# protection.net
KiCad netlist of a schematic drawn in Altium Designer
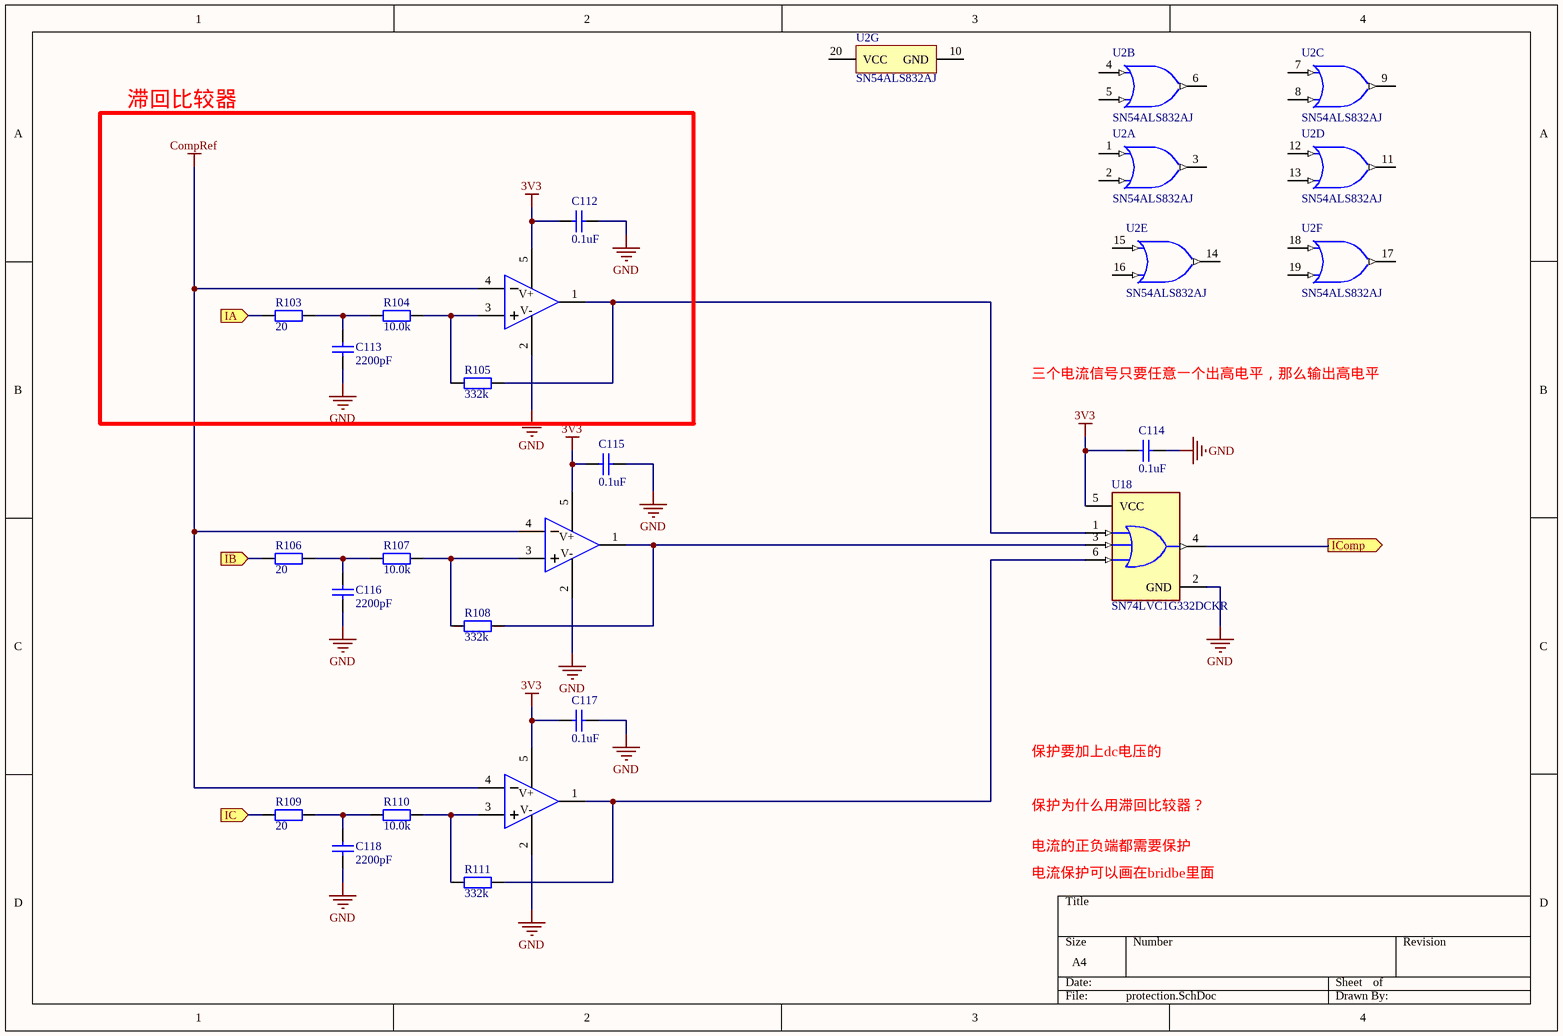
[diagram p0: protection.SchDoc]

(export (version "E")
  (design (tool "Eeschema 10.0.6"))
  (components
    (comp (ref "C112")
      (value "0.1uF")
      (footprint "CAPC1608X06N")
      (description "Capacitor")
      (fields (field (name "PUBLISHER") "Altium Limited"))
      (libsource (lib "Simscale") (part "Cap"))
    )
    (comp (ref "C113")
      (value "2200pF")
      (footprint "CAPC1608X06N")
      (description "Capacitor")
      (fields (field (name "PUBLISHER") "Altium Limited"))
      (libsource (lib "Simscale") (part "Cap"))
    )
    (comp (ref "C114")
      (value "0.1uF")
      (footprint "CAPC1608X06N")
      (description "Capacitor")
      (fields (field (name "PUBLISHER") "Altium Limited"))
      (libsource (lib "Simscale") (part "Cap"))
    )
    (comp (ref "C115")
      (value "0.1uF")
      (footprint "CAPC1608X06N")
      (description "Capacitor")
      (fields (field (name "PUBLISHER") "Altium Limited"))
      (libsource (lib "Simscale") (part "Cap"))
    )
    (comp (ref "C116")
      (value "2200pF")
      (footprint "CAPC1608X06N")
      (description "Capacitor")
      (fields (field (name "PUBLISHER") "Altium Limited"))
      (libsource (lib "Simscale") (part "Cap"))
    )
    (comp (ref "C117")
      (value "0.1uF")
      (footprint "CAPC1608X06N")
      (description "Capacitor")
      (fields (field (name "PUBLISHER") "Altium Limited"))
      (libsource (lib "Simscale") (part "Cap"))
    )
    (comp (ref "C118")
      (value "2200pF")
      (footprint "CAPC1608X06N")
      (description "Capacitor")
      (fields (field (name "PUBLISHER") "Altium Limited"))
      (libsource (lib "Simscale") (part "Cap"))
    )
    (comp (ref "R103")
      (value "20")
      (footprint "RESC1608X05N")
      (description "贴片电阻")
      (libsource (lib "Simscale") (part "0603 100KΩ (1003) 1%_4"))
    )
    (comp (ref "R104")
      (value "10.0k")
      (footprint "RESC1608X05N")
      (description "贴片电阻")
      (libsource (lib "Simscale") (part "0603 100KΩ (1003) 1%_4"))
    )
    (comp (ref "R105")
      (value "332k")
      (footprint "RESC1608X05N")
      (description "贴片电阻")
      (libsource (lib "Simscale") (part "0603 100KΩ (1003) 1%_4"))
    )
    (comp (ref "R106")
      (value "20")
      (footprint "RESC1608X05N")
      (description "贴片电阻")
      (libsource (lib "Simscale") (part "0603 100KΩ (1003) 1%_4"))
    )
    (comp (ref "R107")
      (value "10.0k")
      (footprint "RESC1608X05N")
      (description "贴片电阻")
      (libsource (lib "Simscale") (part "0603 100KΩ (1003) 1%_4"))
    )
    (comp (ref "R108")
      (value "332k")
      (footprint "RESC1608X05N")
      (description "贴片电阻")
      (libsource (lib "Simscale") (part "0603 100KΩ (1003) 1%_4"))
    )
    (comp (ref "R109")
      (value "20")
      (footprint "RESC1608X05N")
      (description "贴片电阻")
      (libsource (lib "Simscale") (part "0603 100KΩ (1003) 1%_4"))
    )
    (comp (ref "R110")
      (value "10.0k")
      (footprint "RESC1608X05N")
      (description "贴片电阻")
      (libsource (lib "Simscale") (part "0603 100KΩ (1003) 1%_4"))
    )
    (comp (ref "R111")
      (value "332k")
      (footprint "RESC1608X05N")
      (description "贴片电阻")
      (libsource (lib "Simscale") (part "0603 100KΩ (1003) 1%_4"))
    )
    (comp (ref "U2")
      (value "SN54ALS832AJ")
      (footprint "J0020A")
      (description "Hex 2-Input OR Drivers, J0020A, TUBE")
      (fields
        (field (name "MANUFACTURER") "Texas Instruments")
        (field (name "GENERIC PART NUMBER") "SN54ALS832A")
      )
      (libsource (lib "Altium Content Vault") (part "TI-SNX4AXX832X-20"))
    )
    (comp (ref "U17")
      (value "TLV3201AIDBVR")
      (footprint "SOT-23-5_L3.0-W1.7-P0.95-LS2.8-BR")
      (fields (field (name "MANUFACTURER") "TI(德州仪器)"))
      (libsource (lib "TLV3201AIDBVR1_TLV3201AIDBVR.schdoc") (part "TLV3201AIDBVR"))
    )
    (comp (ref "U18")
      (value "SN74LVC1G332DCKR")
      (footprint "FP-DCK0006A-MFG")
      (description "IC GATE OR 1CH 3-INP SC70-6")
      (fields
        (field (name "MANUFACTURER") "Texas Instruments")
        (field (name "OCTOPART") "https://octopart.com/sn74lvc1g332dckr-texas+instruments-464861")
      )
      (libsource (lib "Altium Content Vault") (part "a1fbee6839145229a27344b52c53a8d"))
    )
    (comp (ref "U19")
      (value "TLV3201AIDBVR")
      (footprint "SOT-23-5_L3.0-W1.7-P0.95-LS2.8-BR")
      (fields (field (name "MANUFACTURER") "TI(德州仪器)"))
      (libsource (lib "TLV3201AIDBVR1_TLV3201AIDBVR.schdoc") (part "TLV3201AIDBVR"))
    )
    (comp (ref "U20")
      (value "TLV3201AIDBVR")
      (footprint "SOT-23-5_L3.0-W1.7-P0.95-LS2.8-BR")
      (fields (field (name "MANUFACTURER") "TI(德州仪器)"))
      (libsource (lib "TLV3201AIDBVR1_TLV3201AIDBVR.schdoc") (part "TLV3201AIDBVR"))
    )
  )
  (nets
    (net (code "1") (name "/IA") (class "Default")
      (node (ref "R103") (pin "2") (pinfunction "2_2") (pintype "passive"))
    )
    (net (code "2") (name "/IB") (class "Default")
      (node (ref "R106") (pin "2") (pinfunction "2_2") (pintype "passive"))
    )
    (net (code "3") (name "/IC") (class "Default")
      (node (ref "R109") (pin "2") (pinfunction "2_2") (pintype "passive"))
    )
    (net (code "4") (name "/IComp") (class "Default")
      (node (ref "U18") (pin "4") (pinfunction "Y_4") (pintype "output"))
    )
    (net (code "5") (name "3V3") (class "Default")
      (node (ref "C112") (pin "1") (pinfunction "1_1") (pintype "passive"))
      (node (ref "C114") (pin "1") (pinfunction "1_1") (pintype "passive"))
      (node (ref "C115") (pin "1") (pinfunction "1_1") (pintype "passive"))
      (node (ref "C117") (pin "1") (pinfunction "1_1") (pintype "passive"))
      (node (ref "U17") (pin "5") (pinfunction "VCC_5") (pintype "passive"))
      (node (ref "U18") (pin "5") (pinfunction "VCC_5") (pintype "power_in"))
      (node (ref "U19") (pin "5") (pinfunction "VCC_5") (pintype "passive"))
      (node (ref "U20") (pin "5") (pinfunction "VCC_5") (pintype "passive"))
    )
    (net (code "6") (name "CompRef") (class "Default")
      (node (ref "U17") (pin "4") (pinfunction "IN-_4") (pintype "passive"))
      (node (ref "U19") (pin "4") (pinfunction "IN-_4") (pintype "passive"))
      (node (ref "U20") (pin "4") (pinfunction "IN-_4") (pintype "passive"))
    )
    (net (code "7") (name "GND") (class "Default")
      (node (ref "C112") (pin "2") (pinfunction "2_2") (pintype "passive"))
      (node (ref "C113") (pin "2") (pinfunction "2_2") (pintype "passive"))
      (node (ref "C114") (pin "2") (pinfunction "2_2") (pintype "passive"))
      (node (ref "C115") (pin "2") (pinfunction "2_2") (pintype "passive"))
      (node (ref "C116") (pin "2") (pinfunction "2_2") (pintype "passive"))
      (node (ref "C117") (pin "2") (pinfunction "2_2") (pintype "passive"))
      (node (ref "C118") (pin "2") (pinfunction "2_2") (pintype "passive"))
      (node (ref "U17") (pin "2") (pinfunction "GND_2") (pintype "passive"))
      (node (ref "U18") (pin "2") (pinfunction "GND_2") (pintype "power_in"))
      (node (ref "U19") (pin "2") (pinfunction "GND_2") (pintype "passive"))
      (node (ref "U20") (pin "2") (pinfunction "GND_2") (pintype "passive"))
    )
    (net (code "8") (name "Net-(C113-Pad1)") (class "Default")
      (node (ref "C113") (pin "1") (pinfunction "1_1") (pintype "passive"))
      (node (ref "R103") (pin "1") (pinfunction "1_1") (pintype "passive"))
      (node (ref "R104") (pin "2") (pinfunction "2_2") (pintype "passive"))
    )
    (net (code "9") (name "Net-(C116-Pad1)") (class "Default")
      (node (ref "C116") (pin "1") (pinfunction "1_1") (pintype "passive"))
      (node (ref "R106") (pin "1") (pinfunction "1_1") (pintype "passive"))
      (node (ref "R107") (pin "2") (pinfunction "2_2") (pintype "passive"))
    )
    (net (code "10") (name "Net-(C118-Pad1)") (class "Default")
      (node (ref "C118") (pin "1") (pinfunction "1_1") (pintype "passive"))
      (node (ref "R109") (pin "1") (pinfunction "1_1") (pintype "passive"))
      (node (ref "R110") (pin "2") (pinfunction "2_2") (pintype "passive"))
    )
    (net (code "11") (name "Net-(U17-IN+)") (class "Default")
      (node (ref "R104") (pin "1") (pinfunction "1_1") (pintype "passive"))
      (node (ref "R105") (pin "2") (pinfunction "2_2") (pintype "passive"))
      (node (ref "U17") (pin "3") (pinfunction "IN+_3") (pintype "passive"))
    )
    (net (code "12") (name "Net-(U17-OUT)") (class "Default")
      (node (ref "R105") (pin "1") (pinfunction "1_1") (pintype "passive"))
      (node (ref "U17") (pin "1") (pinfunction "OUT_1") (pintype "passive"))
      (node (ref "U18") (pin "1") (pinfunction "A_1") (pintype "input"))
    )
    (net (code "13") (name "Net-(U18-B)") (class "Default")
      (node (ref "R108") (pin "1") (pinfunction "1_1") (pintype "passive"))
      (node (ref "U18") (pin "3") (pinfunction "B_3") (pintype "input"))
      (node (ref "U19") (pin "1") (pinfunction "OUT_1") (pintype "passive"))
    )
    (net (code "14") (name "Net-(U18-C)") (class "Default")
      (node (ref "R111") (pin "1") (pinfunction "1_1") (pintype "passive"))
      (node (ref "U18") (pin "6") (pinfunction "C_6") (pintype "input"))
      (node (ref "U20") (pin "1") (pinfunction "OUT_1") (pintype "passive"))
    )
    (net (code "15") (name "Net-(U19-IN+)") (class "Default")
      (node (ref "R107") (pin "1") (pinfunction "1_1") (pintype "passive"))
      (node (ref "R108") (pin "2") (pinfunction "2_2") (pintype "passive"))
      (node (ref "U19") (pin "3") (pinfunction "IN+_3") (pintype "passive"))
    )
    (net (code "16") (name "Net-(U20-IN+)") (class "Default")
      (node (ref "R110") (pin "1") (pinfunction "1_1") (pintype "passive"))
      (node (ref "R111") (pin "2") (pinfunction "2_2") (pintype "passive"))
      (node (ref "U20") (pin "3") (pinfunction "IN+_3") (pintype "passive"))
    )
    (net (code "17") (name "unconnected-(U2A-1A-Pad1)") (class "Default")
      (node (ref "U2") (pin "1") (pinfunction "1A_1") (pintype "input"))
    )
    (net (code "18") (name "unconnected-(U2A-1B-Pad2)") (class "Default")
      (node (ref "U2") (pin "2") (pinfunction "1B_2") (pintype "input"))
    )
    (net (code "19") (name "unconnected-(U2A-1Y-Pad3)") (class "Default")
      (node (ref "U2") (pin "3") (pinfunction "1Y_3") (pintype "output"))
    )
    (net (code "20") (name "unconnected-(U2B-2A-Pad4)") (class "Default")
      (node (ref "U2") (pin "4") (pinfunction "2A_4") (pintype "input"))
    )
    (net (code "21") (name "unconnected-(U2B-2B-Pad5)") (class "Default")
      (node (ref "U2") (pin "5") (pinfunction "2B_5") (pintype "input"))
    )
    (net (code "22") (name "unconnected-(U2B-2Y-Pad6)") (class "Default")
      (node (ref "U2") (pin "6") (pinfunction "2Y_6") (pintype "output"))
    )
    (net (code "23") (name "unconnected-(U2C-3A-Pad7)") (class "Default")
      (node (ref "U2") (pin "7") (pinfunction "3A_7") (pintype "input"))
    )
    (net (code "24") (name "unconnected-(U2C-3B-Pad8)") (class "Default")
      (node (ref "U2") (pin "8") (pinfunction "3B_8") (pintype "input"))
    )
    (net (code "25") (name "unconnected-(U2C-3Y-Pad9)") (class "Default")
      (node (ref "U2") (pin "9") (pinfunction "3Y_9") (pintype "output"))
    )
    (net (code "26") (name "unconnected-(U2D-4A-Pad12)") (class "Default")
      (node (ref "U2") (pin "12") (pinfunction "4A_12") (pintype "input"))
    )
    (net (code "27") (name "unconnected-(U2D-4B-Pad13)") (class "Default")
      (node (ref "U2") (pin "13") (pinfunction "4B_13") (pintype "input"))
    )
    (net (code "28") (name "unconnected-(U2D-4Y-Pad11)") (class "Default")
      (node (ref "U2") (pin "11") (pinfunction "4Y_11") (pintype "output"))
    )
    (net (code "29") (name "unconnected-(U2E-5A-Pad15)") (class "Default")
      (node (ref "U2") (pin "15") (pinfunction "5A_15") (pintype "input"))
    )
    (net (code "30") (name "unconnected-(U2E-5B-Pad16)") (class "Default")
      (node (ref "U2") (pin "16") (pinfunction "5B_16") (pintype "input"))
    )
    (net (code "31") (name "unconnected-(U2E-5Y-Pad14)") (class "Default")
      (node (ref "U2") (pin "14") (pinfunction "5Y_14") (pintype "output"))
    )
    (net (code "32") (name "unconnected-(U2F-6A-Pad18)") (class "Default")
      (node (ref "U2") (pin "18") (pinfunction "6A_18") (pintype "input"))
    )
    (net (code "33") (name "unconnected-(U2F-6B-Pad19)") (class "Default")
      (node (ref "U2") (pin "19") (pinfunction "6B_19") (pintype "input"))
    )
    (net (code "34") (name "unconnected-(U2F-6Y-Pad17)") (class "Default")
      (node (ref "U2") (pin "17") (pinfunction "6Y_17") (pintype "output"))
    )
    (net (code "35") (name "unconnected-(U2G-GND-Pad10)") (class "Default")
      (node (ref "U2") (pin "10") (pinfunction "GND_10") (pintype "power_in"))
    )
    (net (code "36") (name "unconnected-(U2G-VCC-Pad20)") (class "Default")
      (node (ref "U2") (pin "20") (pinfunction "VCC_20") (pintype "power_in"))
    )
  )
)
